# DotControl.net
KiCad netlist of a schematic drawn in EAGLE
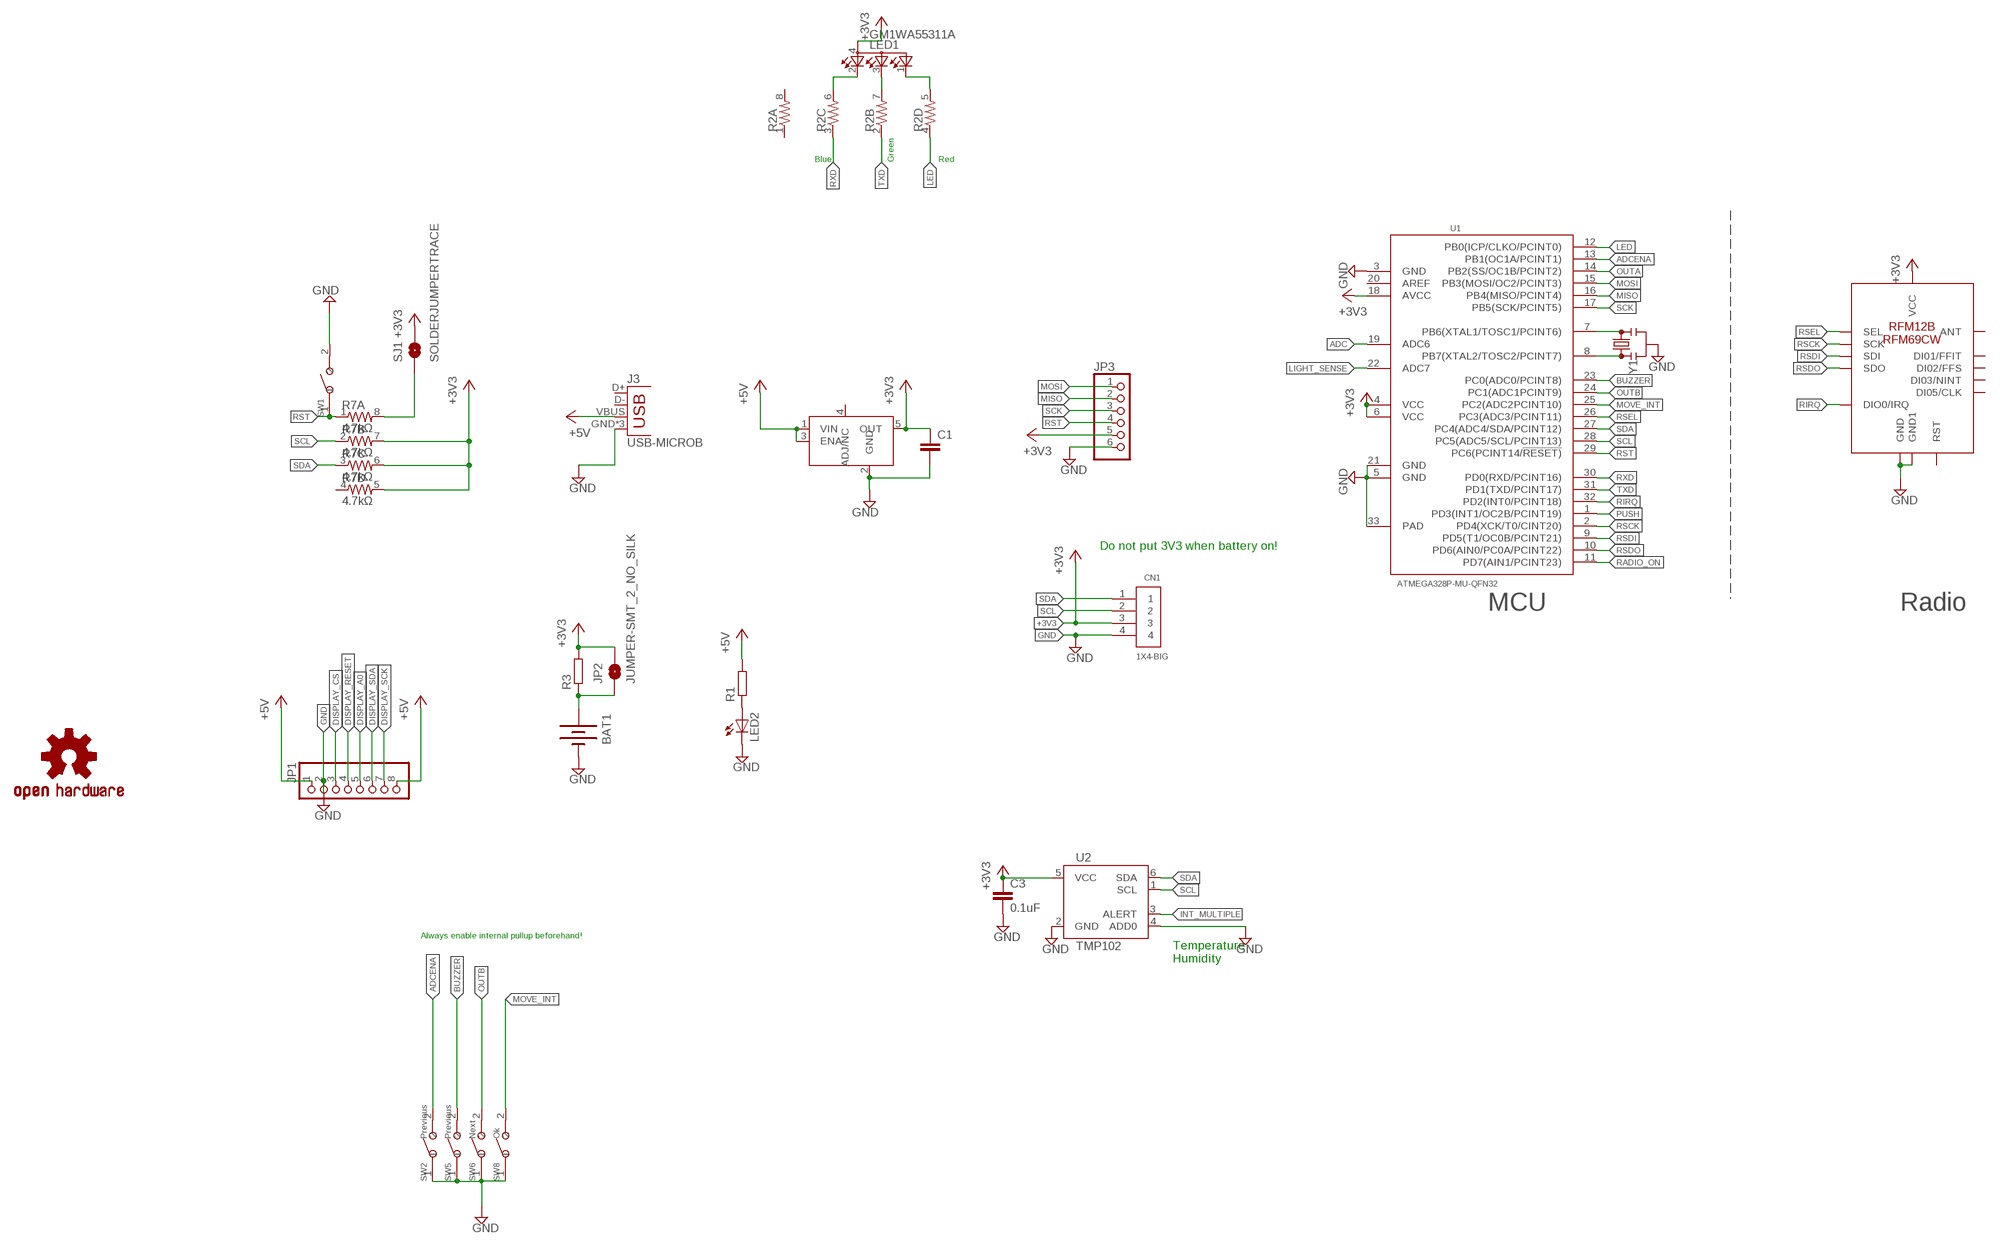
[diagram p0: schematic, sheet 1]

(export (version "E")
  (design (tool "Eeschema 10.0.6"))
  (components
    (comp (ref "BAT1")
      (value "BATTERY20PTH")
      (footprint "eagle-import:BATTCOM_20MM_PTH")
      (libsource (lib "eagle-import") (part "BATTERY20PTH"))
    )
    (comp (ref "C1")
      (value "C-EUC0603")
      (footprint "eagle-import:C0603")
      (libsource (lib "eagle-import") (part "C-EUC0603"))
    )
    (comp (ref "C3")
      (value "0.1uF")
      (footprint "eagle-import:C0603")
      (libsource (lib "eagle-import") (part "resistor_C-EUC0603"))
    )
    (comp (ref "CN1")
      (value "1X4-BIG")
      (footprint "eagle-import:1X04-BIG")
      (libsource (lib "eagle-import") (part "1X4-BIG"))
    )
    (comp (ref "J3")
      (value "USB-MICROB")
      (footprint "eagle-import:USB-MICROB")
      (libsource (lib "eagle-import") (part "USB-MICROB"))
    )
    (comp (ref "JP1")
      (value "PINHD-1X8CLEANBIG")
      (footprint "eagle-import:1X08-CLEANBIG")
      (libsource (lib "eagle-import") (part "PINHD-1X8CLEANBIG"))
    )
    (comp (ref "JP2")
      (value "JUMPER-SMT_2_NO_SILK")
      (footprint "eagle-import:SMT-JUMPER_2_NO_SILK")
      (libsource (lib "eagle-import") (part "JUMPER-SMT_2_NO_SILK"))
    )
    (comp (ref "JP3")
      (value "PINHD-1X6")
      (footprint "eagle-import:1X06")
      (libsource (lib "eagle-import") (part "PINHD-1X6"))
    )
    (comp (ref "LED1")
      (value "GM1WA55311A")
      (footprint "eagle-import:GM1WA55311A")
      (libsource (lib "eagle-import") (part "GM1WA55311A"))
    )
    (comp (ref "LED2")
      (value "LED0603")
      (footprint "eagle-import:LED-0603")
      (libsource (lib "eagle-import") (part "LED0603"))
    )
    (comp (ref "R1")
      (value "R-EU_R0603")
      (footprint "eagle-import:R0603")
      (libsource (lib "eagle-import") (part "R-EU_R0603"))
    )
    (comp (ref "R2")
      (value "RESISTOR-ARRAY0603-ARV")
      (footprint "eagle-import:0603-ARV")
      (libsource (lib "eagle-import") (part "RESISTOR-ARRAY0603-ARV"))
    )
    (comp (ref "R3")
      (value "R-EU_R0603")
      (footprint "eagle-import:R0603")
      (libsource (lib "eagle-import") (part "R-EU_R0603"))
    )
    (comp (ref "R7")
      (value "4.7kΩ")
      (footprint "eagle-import:0603-ARV")
      (libsource (lib "eagle-import") (part "RESISTOR-ARRAY0603-ARV"))
    )
    (comp (ref "SJ1")
      (value "SOLDERJUMPERTRACE")
      (footprint "eagle-import:SJ_2S-TRACE")
      (libsource (lib "eagle-import") (part "SOLDERJUMPERTRACE"))
    )
    (comp (ref "SW1")
      (value "SMD-BUTTON(2P-6.0X3.0X2.5MM)-DHT-1163S")
      (footprint "eagle-import:SW2-4.0-6.0X3.0X2.5MM")
      (libsource (lib "eagle-import") (part "SMD-BUTTON(2P-6.0X3.0X2.5MM)-DHT-1163S"))
    )
    (comp (ref "SW2")
      (value "Previous")
      (footprint "eagle-import:SW2-4.0-6.0X3.0X2.5MM")
      (libsource (lib "eagle-import") (part "SMD-BUTTON(2P-6.0X3.0X2.5MM)-DHT-1163S"))
    )
    (comp (ref "SW5")
      (value "Previous")
      (footprint "eagle-import:SW2-4.0-6.0X3.0X2.5MM")
      (libsource (lib "eagle-import") (part "SMD-BUTTON(2P-6.0X3.0X2.5MM)-DHT-1163S"))
    )
    (comp (ref "SW6")
      (value "Next")
      (footprint "eagle-import:SW2-4.0-6.0X3.0X2.5MM")
      (libsource (lib "eagle-import") (part "SMD-BUTTON(2P-6.0X3.0X2.5MM)-DHT-1163S"))
    )
    (comp (ref "SW8")
      (value "Ok")
      (footprint "eagle-import:SW2-4.0-6.0X3.0X2.5MM")
      (libsource (lib "eagle-import") (part "SMD-BUTTON(2P-6.0X3.0X2.5MM)-DHT-1163S"))
    )
    (comp (ref "U$1")
      (value "RFM12B/69CW")
      (footprint "eagle-import:RFM12B_69CW")
      (libsource (lib "eagle-import") (part "RFM12B/69CW"))
    )
    (comp (ref "U$2")
      (value "OSHW-LOGOL")
      (footprint "eagle-import:OSHW-LOGO-L")
      (libsource (lib "eagle-import") (part "OSHW-LOGOL"))
    )
    (comp (ref "U$4")
      (value "LDCL015")
      (footprint "eagle-import:SOT23-5")
      (libsource (lib "eagle-import") (part "LDCL015"))
    )
    (comp (ref "U1")
      (value "ATMEGA328P-MU-QFN32")
      (footprint "eagle-import:QFN32G-0.5-5X5MM")
      (fields (field (name "MPN") "ATMEGA328P-MU"))
      (libsource (lib "eagle-import") (part "MCU-ATMEGA328P-MU(QFN32)"))
    )
    (comp (ref "U2")
      (value "TMP102")
      (footprint "eagle-import:SOT563")
      (libsource (lib "eagle-import") (part "TMP102"))
    )
    (comp (ref "Y1")
      (value "RESONATORSMD-3.2X1.3")
      (footprint "eagle-import:RESONATOR-SMD-3.2X1.3")
      (libsource (lib "eagle-import") (part "RESONATORSMD-3.2X1.3"))
    )
  )
  (nets
    (net (code "1") (name "+3V3") (class "Default")
      (node (ref "C1") (pin "1") (pinfunction "1_1") (pintype "passive"))
      (node (ref "C3") (pin "1") (pinfunction "1_1") (pintype "passive"))
      (node (ref "CN1") (pin "3") (pinfunction "3_3") (pintype "bidirectional"))
      (node (ref "JP2") (pin "2") (pinfunction "2_2") (pintype "passive"))
      (node (ref "JP3") (pin "5") (pinfunction "5_5") (pintype "passive"))
      (node (ref "LED1") (pin "4") (pinfunction "A_4") (pintype "passive"))
      (node (ref "R3") (pin "2") (pinfunction "2_2") (pintype "passive"))
      (node (ref "R7") (pin "5") (pinfunction "2_5") (pintype "passive"))
      (node (ref "R7") (pin "6") (pinfunction "2_6") (pintype "passive"))
      (node (ref "R7") (pin "7") (pinfunction "2_7") (pintype "passive"))
      (node (ref "SJ1") (pin "2") (pinfunction "2_2") (pintype "passive"))
      (node (ref "U$1") (pin "VDD") (pinfunction "VCC_VDD") (pintype "power_in"))
      (node (ref "U$4") (pin "5") (pinfunction "OUT_5") (pintype "bidirectional"))
      (node (ref "U1") (pin "18") (pinfunction "AVCC_18") (pintype "bidirectional"))
      (node (ref "U1") (pin "4") (pinfunction "VCC_4") (pintype "bidirectional"))
      (node (ref "U1") (pin "6") (pinfunction "VCC_6") (pintype "bidirectional"))
      (node (ref "U2") (pin "5") (pinfunction "VCC_5") (pintype "bidirectional"))
    )
    (net (code "2") (name "+5V") (class "Default")
      (node (ref "J3") (pin "VBUS") (pinfunction "VBUS_VBUS") (pintype "bidirectional"))
      (node (ref "JP1") (pin "1") (pinfunction "1_1") (pintype "passive"))
      (node (ref "JP1") (pin "8") (pinfunction "8_8") (pintype "passive"))
      (node (ref "R1") (pin "2") (pinfunction "2_2") (pintype "passive"))
      (node (ref "U$4") (pin "1") (pinfunction "VIN_1") (pintype "bidirectional"))
      (node (ref "U$4") (pin "3") (pinfunction "ENA_3") (pintype "bidirectional"))
    )
    (net (code "3") (name "ADC") (class "Default")
      (node (ref "U1") (pin "19") (pinfunction "ADC6_19") (pintype "bidirectional"))
    )
    (net (code "4") (name "ADCENA") (class "Default")
      (node (ref "SW2") (pin "2") (pinfunction "2_2") (pintype "bidirectional"))
      (node (ref "U1") (pin "13") (pinfunction "PB1(OC1A/PCINT1)_13") (pintype "bidirectional"))
    )
    (net (code "5") (name "BUZZER") (class "Default")
      (node (ref "SW5") (pin "2") (pinfunction "2_2") (pintype "bidirectional"))
      (node (ref "U1") (pin "23") (pinfunction "PC0(ADC0/PCINT8)_23") (pintype "bidirectional"))
    )
    (net (code "6") (name "DISPLAY_A0") (class "Default")
      (node (ref "JP1") (pin "5") (pinfunction "5_5") (pintype "passive"))
    )
    (net (code "7") (name "DISPLAY_CS") (class "Default")
      (node (ref "JP1") (pin "3") (pinfunction "3_3") (pintype "passive"))
    )
    (net (code "8") (name "DISPLAY_RESET") (class "Default")
      (node (ref "JP1") (pin "4") (pinfunction "4_4") (pintype "passive"))
    )
    (net (code "9") (name "DISPLAY_SCK") (class "Default")
      (node (ref "JP1") (pin "7") (pinfunction "7_7") (pintype "passive"))
    )
    (net (code "10") (name "DISPLAY_SDA") (class "Default")
      (node (ref "JP1") (pin "6") (pinfunction "6_6") (pintype "passive"))
    )
    (net (code "11") (name "GND") (class "Default")
      (node (ref "BAT1") (pin "2") (pinfunction "-_2") (pintype "power_in"))
      (node (ref "C1") (pin "2") (pinfunction "2_2") (pintype "passive"))
      (node (ref "C3") (pin "2") (pinfunction "2_2") (pintype "passive"))
      (node (ref "CN1") (pin "4") (pinfunction "4_4") (pintype "bidirectional"))
      (node (ref "J3") (pin "GND") (pinfunction "GND_GND") (pintype "bidirectional"))
      (node (ref "J3") (pin "MT1") (pinfunction "GND_MT1") (pintype "bidirectional"))
      (node (ref "J3") (pin "MT2") (pinfunction "GND_MT2") (pintype "bidirectional"))
      (node (ref "JP1") (pin "2") (pinfunction "2_2") (pintype "passive"))
      (node (ref "JP3") (pin "6") (pinfunction "6_6") (pintype "passive"))
      (node (ref "LED2") (pin "C") (pinfunction "C_C") (pintype "passive"))
      (node (ref "SW1") (pin "2") (pinfunction "2_2") (pintype "bidirectional"))
      (node (ref "SW2") (pin "1") (pinfunction "1_1") (pintype "bidirectional"))
      (node (ref "SW5") (pin "1") (pinfunction "1_1") (pintype "bidirectional"))
      (node (ref "SW6") (pin "1") (pinfunction "1_1") (pintype "bidirectional"))
      (node (ref "SW8") (pin "1") (pinfunction "1_1") (pintype "bidirectional"))
      (node (ref "U$1") (pin "GND") (pinfunction "GND_GND") (pintype "power_in"))
      (node (ref "U$1") (pin "GND1") (pinfunction "GND1_GND1") (pintype "power_in"))
      (node (ref "U$4") (pin "2") (pinfunction "GND_2") (pintype "bidirectional"))
      (node (ref "U1") (pin "21") (pinfunction "GND_21") (pintype "bidirectional"))
      (node (ref "U1") (pin "3") (pinfunction "GND_3") (pintype "bidirectional"))
      (node (ref "U1") (pin "33") (pinfunction "PAD_33") (pintype "bidirectional"))
      (node (ref "U1") (pin "5") (pinfunction "GND_5") (pintype "bidirectional"))
      (node (ref "U2") (pin "2") (pinfunction "GND_2") (pintype "bidirectional"))
      (node (ref "U2") (pin "4") (pinfunction "ADD0_4") (pintype "bidirectional"))
      (node (ref "Y1") (pin "2") (pinfunction "2_2") (pintype "passive"))
    )
    (net (code "12") (name "INT_MULTIPLE") (class "Default")
      (node (ref "U2") (pin "3") (pinfunction "ALERT_3") (pintype "bidirectional"))
    )
    (net (code "13") (name "LED") (class "Default")
      (node (ref "R2") (pin "4") (pinfunction "1_4") (pintype "passive"))
      (node (ref "U1") (pin "12") (pinfunction "PB0(ICP/CLKO/PCINT0)_12") (pintype "bidirectional"))
    )
    (net (code "14") (name "LIGHT_SENSE") (class "Default")
      (node (ref "U1") (pin "22") (pinfunction "ADC7_22") (pintype "bidirectional"))
    )
    (net (code "15") (name "MISO") (class "Default")
      (node (ref "JP3") (pin "2") (pinfunction "2_2") (pintype "passive"))
      (node (ref "U1") (pin "16") (pinfunction "PB4(MISO/PCINT4)_16") (pintype "bidirectional"))
    )
    (net (code "16") (name "MOSI") (class "Default")
      (node (ref "JP3") (pin "1") (pinfunction "1_1") (pintype "passive"))
      (node (ref "U1") (pin "15") (pinfunction "PB3(MOSI/OC2/PCINT3)_15") (pintype "bidirectional"))
    )
    (net (code "17") (name "MOVE_INT") (class "Default")
      (node (ref "SW8") (pin "2") (pinfunction "2_2") (pintype "bidirectional"))
      (node (ref "U1") (pin "25") (pinfunction "PC2(ADC2PCINT10)_25") (pintype "bidirectional"))
    )
    (net (code "18") (name "Net-(BAT1-+)") (class "Default")
      (node (ref "BAT1") (pin "1") (pinfunction "+_1") (pintype "power_in"))
      (node (ref "JP2") (pin "1") (pinfunction "1_1") (pintype "passive"))
      (node (ref "R3") (pin "1") (pinfunction "1_1") (pintype "passive"))
    )
    (net (code "19") (name "Net-(LED1-CBLUE)") (class "Default")
      (node (ref "LED1") (pin "3") (pinfunction "CBLUE_3") (pintype "passive"))
      (node (ref "R2") (pin "7") (pinfunction "2_7") (pintype "passive"))
    )
    (net (code "20") (name "Net-(LED1-CGREEN)") (class "Default")
      (node (ref "LED1") (pin "1") (pinfunction "CGREEN_1") (pintype "passive"))
      (node (ref "R2") (pin "5") (pinfunction "2_5") (pintype "passive"))
    )
    (net (code "21") (name "Net-(LED1-CRED)") (class "Default")
      (node (ref "LED1") (pin "2") (pinfunction "CRED_2") (pintype "passive"))
      (node (ref "R2") (pin "6") (pinfunction "2_6") (pintype "passive"))
    )
    (net (code "22") (name "Net-(LED2-PadA)") (class "Default")
      (node (ref "LED2") (pin "A") (pinfunction "A_A") (pintype "passive"))
      (node (ref "R1") (pin "1") (pinfunction "1_1") (pintype "passive"))
    )
    (net (code "23") (name "Net-(R7A-2)") (class "Default")
      (node (ref "R7") (pin "8") (pinfunction "2_8") (pintype "passive"))
      (node (ref "SJ1") (pin "1") (pinfunction "1_1") (pintype "passive"))
    )
    (net (code "24") (name "Net-(U1-PB6(XTAL1{slash}TOSC1{slash}PCINT6))") (class "Default")
      (node (ref "U1") (pin "7") (pinfunction "PB6(XTAL1/TOSC1/PCINT6)_7") (pintype "bidirectional"))
      (node (ref "Y1") (pin "3") (pinfunction "3_3") (pintype "passive"))
    )
    (net (code "25") (name "Net-(U1-PB7(XTAL2{slash}TOSC2{slash}PCINT7))") (class "Default")
      (node (ref "U1") (pin "8") (pinfunction "PB7(XTAL2/TOSC2/PCINT7)_8") (pintype "bidirectional"))
      (node (ref "Y1") (pin "1") (pinfunction "1_1") (pintype "passive"))
    )
    (net (code "26") (name "OUTA") (class "Default")
      (node (ref "U1") (pin "14") (pinfunction "PB2(SS/OC1B/PCINT2)_14") (pintype "bidirectional"))
    )
    (net (code "27") (name "OUTB") (class "Default")
      (node (ref "SW6") (pin "2") (pinfunction "2_2") (pintype "bidirectional"))
      (node (ref "U1") (pin "24") (pinfunction "PC1(ADC1PCINT9)_24") (pintype "bidirectional"))
    )
    (net (code "28") (name "PUSH") (class "Default")
      (node (ref "U1") (pin "1") (pinfunction "PD3(INT1/OC2B/PCINT19)_1") (pintype "bidirectional"))
    )
    (net (code "29") (name "RADIO_ON") (class "Default")
      (node (ref "U1") (pin "11") (pinfunction "PD7(AIN1/PCINT23)_11") (pintype "bidirectional"))
    )
    (net (code "30") (name "RIRQ") (class "Default")
      (node (ref "U$1") (pin "IRQ") (pinfunction "DIO0/IRQ_IRQ") (pintype "open_collector"))
      (node (ref "U1") (pin "32") (pinfunction "PD2(INT0/PCINT18)_32") (pintype "bidirectional"))
    )
    (net (code "31") (name "RSCK") (class "Default")
      (node (ref "U$1") (pin "SCK") (pinfunction "SCK_SCK") (pintype "input"))
      (node (ref "U1") (pin "2") (pinfunction "PD4(XCK/T0/CINT20)_2") (pintype "bidirectional"))
    )
    (net (code "32") (name "RSDI") (class "Default")
      (node (ref "U$1") (pin "SDI") (pinfunction "SDI_SDI") (pintype "input"))
      (node (ref "U1") (pin "9") (pinfunction "PD5(T1/OC0B/PCINT21)_9") (pintype "bidirectional"))
    )
    (net (code "33") (name "RSDO") (class "Default")
      (node (ref "U$1") (pin "SDO") (pinfunction "SDO_SDO") (pintype "output"))
      (node (ref "U1") (pin "10") (pinfunction "PD6(AIN0/PC0A/PCINT22)_10") (pintype "bidirectional"))
    )
    (net (code "34") (name "RSEL") (class "Default")
      (node (ref "U$1") (pin "SEL") (pinfunction "SEL_SEL") (pintype "input"))
      (node (ref "U1") (pin "26") (pinfunction "PC3(ADC3/PCINT11)_26") (pintype "bidirectional"))
    )
    (net (code "35") (name "RST") (class "Default")
      (node (ref "JP3") (pin "4") (pinfunction "4_4") (pintype "passive"))
      (node (ref "R7") (pin "1") (pinfunction "1_1") (pintype "passive"))
      (node (ref "SW1") (pin "1") (pinfunction "1_1") (pintype "bidirectional"))
      (node (ref "U1") (pin "29") (pinfunction "PC6(PCINT14/~{RESET})_29") (pintype "bidirectional"))
    )
    (net (code "36") (name "RXD") (class "Default")
      (node (ref "R2") (pin "3") (pinfunction "1_3") (pintype "passive"))
      (node (ref "U1") (pin "30") (pinfunction "PD0(RXD/PCINT16)_30") (pintype "bidirectional"))
    )
    (net (code "37") (name "SCK") (class "Default")
      (node (ref "JP3") (pin "3") (pinfunction "3_3") (pintype "passive"))
      (node (ref "U1") (pin "17") (pinfunction "PB5(SCK/PCINT5)_17") (pintype "bidirectional"))
    )
    (net (code "38") (name "SCL") (class "Default")
      (node (ref "CN1") (pin "2") (pinfunction "2_2") (pintype "bidirectional"))
      (node (ref "R7") (pin "2") (pinfunction "1_2") (pintype "passive"))
      (node (ref "U1") (pin "28") (pinfunction "PC5(ADC5/SCL/PCINT13)_28") (pintype "bidirectional"))
      (node (ref "U2") (pin "1") (pinfunction "SCL_1") (pintype "bidirectional"))
    )
    (net (code "39") (name "SDA") (class "Default")
      (node (ref "CN1") (pin "1") (pinfunction "1_1") (pintype "bidirectional"))
      (node (ref "R7") (pin "3") (pinfunction "1_3") (pintype "passive"))
      (node (ref "U1") (pin "27") (pinfunction "PC4(ADC4/SDA/PCINT12)_27") (pintype "bidirectional"))
      (node (ref "U2") (pin "6") (pinfunction "SDA_6") (pintype "bidirectional"))
    )
    (net (code "40") (name "TXD") (class "Default")
      (node (ref "R2") (pin "2") (pinfunction "1_2") (pintype "passive"))
      (node (ref "U1") (pin "31") (pinfunction "PD1(TXD/PCINT17)_31") (pintype "bidirectional"))
    )
    (net (code "41") (name "unconnected-(J3-PadD+)") (class "Default")
      (node (ref "J3") (pin "D+") (pinfunction "D+_D+") (pintype "bidirectional"))
    )
    (net (code "42") (name "unconnected-(J3-PadD-)") (class "Default")
      (node (ref "J3") (pin "D-") (pinfunction "D-_D-") (pintype "bidirectional"))
    )
    (net (code "43") (name "unconnected-(R2-Pad1)") (class "Default")
      (node (ref "R2") (pin "1") (pinfunction "1_1") (pintype "passive"))
    )
    (net (code "44") (name "unconnected-(R2A-2-Pad8)") (class "Default")
      (node (ref "R2") (pin "8") (pinfunction "2_8") (pintype "passive"))
    )
    (net (code "45") (name "unconnected-(R7D-1-Pad4)") (class "Default")
      (node (ref "R7") (pin "4") (pinfunction "1_4") (pintype "passive"))
    )
    (net (code "46") (name "unconnected-(U$1-DI01{slash}FFIT-PadFFIT)") (class "Default")
      (node (ref "U$1") (pin "FFIT") (pinfunction "DI01/FFIT_FFIT") (pintype "passive"))
    )
    (net (code "47") (name "unconnected-(U$1-DI02{slash}FFS-PadFFS)") (class "Default")
      (node (ref "U$1") (pin "FFS") (pinfunction "DI02/FFS_FFS") (pintype "bidirectional"))
    )
    (net (code "48") (name "unconnected-(U$1-DI03{slash}NINT-PadNINT)") (class "Default")
      (node (ref "U$1") (pin "NINT") (pinfunction "DI03/NINT_NINT") (pintype "passive"))
    )
    (net (code "49") (name "unconnected-(U$1-DI05{slash}CLK-PadCLK)") (class "Default")
      (node (ref "U$1") (pin "CLK") (pinfunction "DI05/CLK_CLK") (pintype "passive"))
    )
    (net (code "50") (name "unconnected-(U$1-PadANT)") (class "Default")
      (node (ref "U$1") (pin "ANT") (pinfunction "ANT_ANT") (pintype "passive"))
    )
    (net (code "51") (name "unconnected-(U$1-PadRST)") (class "Default")
      (node (ref "U$1") (pin "RST") (pinfunction "RST_RST") (pintype "open_collector"))
    )
    (net (code "52") (name "unconnected-(U$4-ADJ{slash}NC-Pad4)") (class "Default")
      (node (ref "U$4") (pin "4") (pinfunction "ADJ/NC_4") (pintype "bidirectional"))
    )
    (net (code "53") (name "unconnected-(U1-AREF-Pad20)") (class "Default")
      (node (ref "U1") (pin "20") (pinfunction "AREF_20") (pintype "bidirectional"))
    )
  )
)
